# opendeep_pba001_eval_v01.net
KiCad netlist of a schematic drawn in EasyEDA Pro
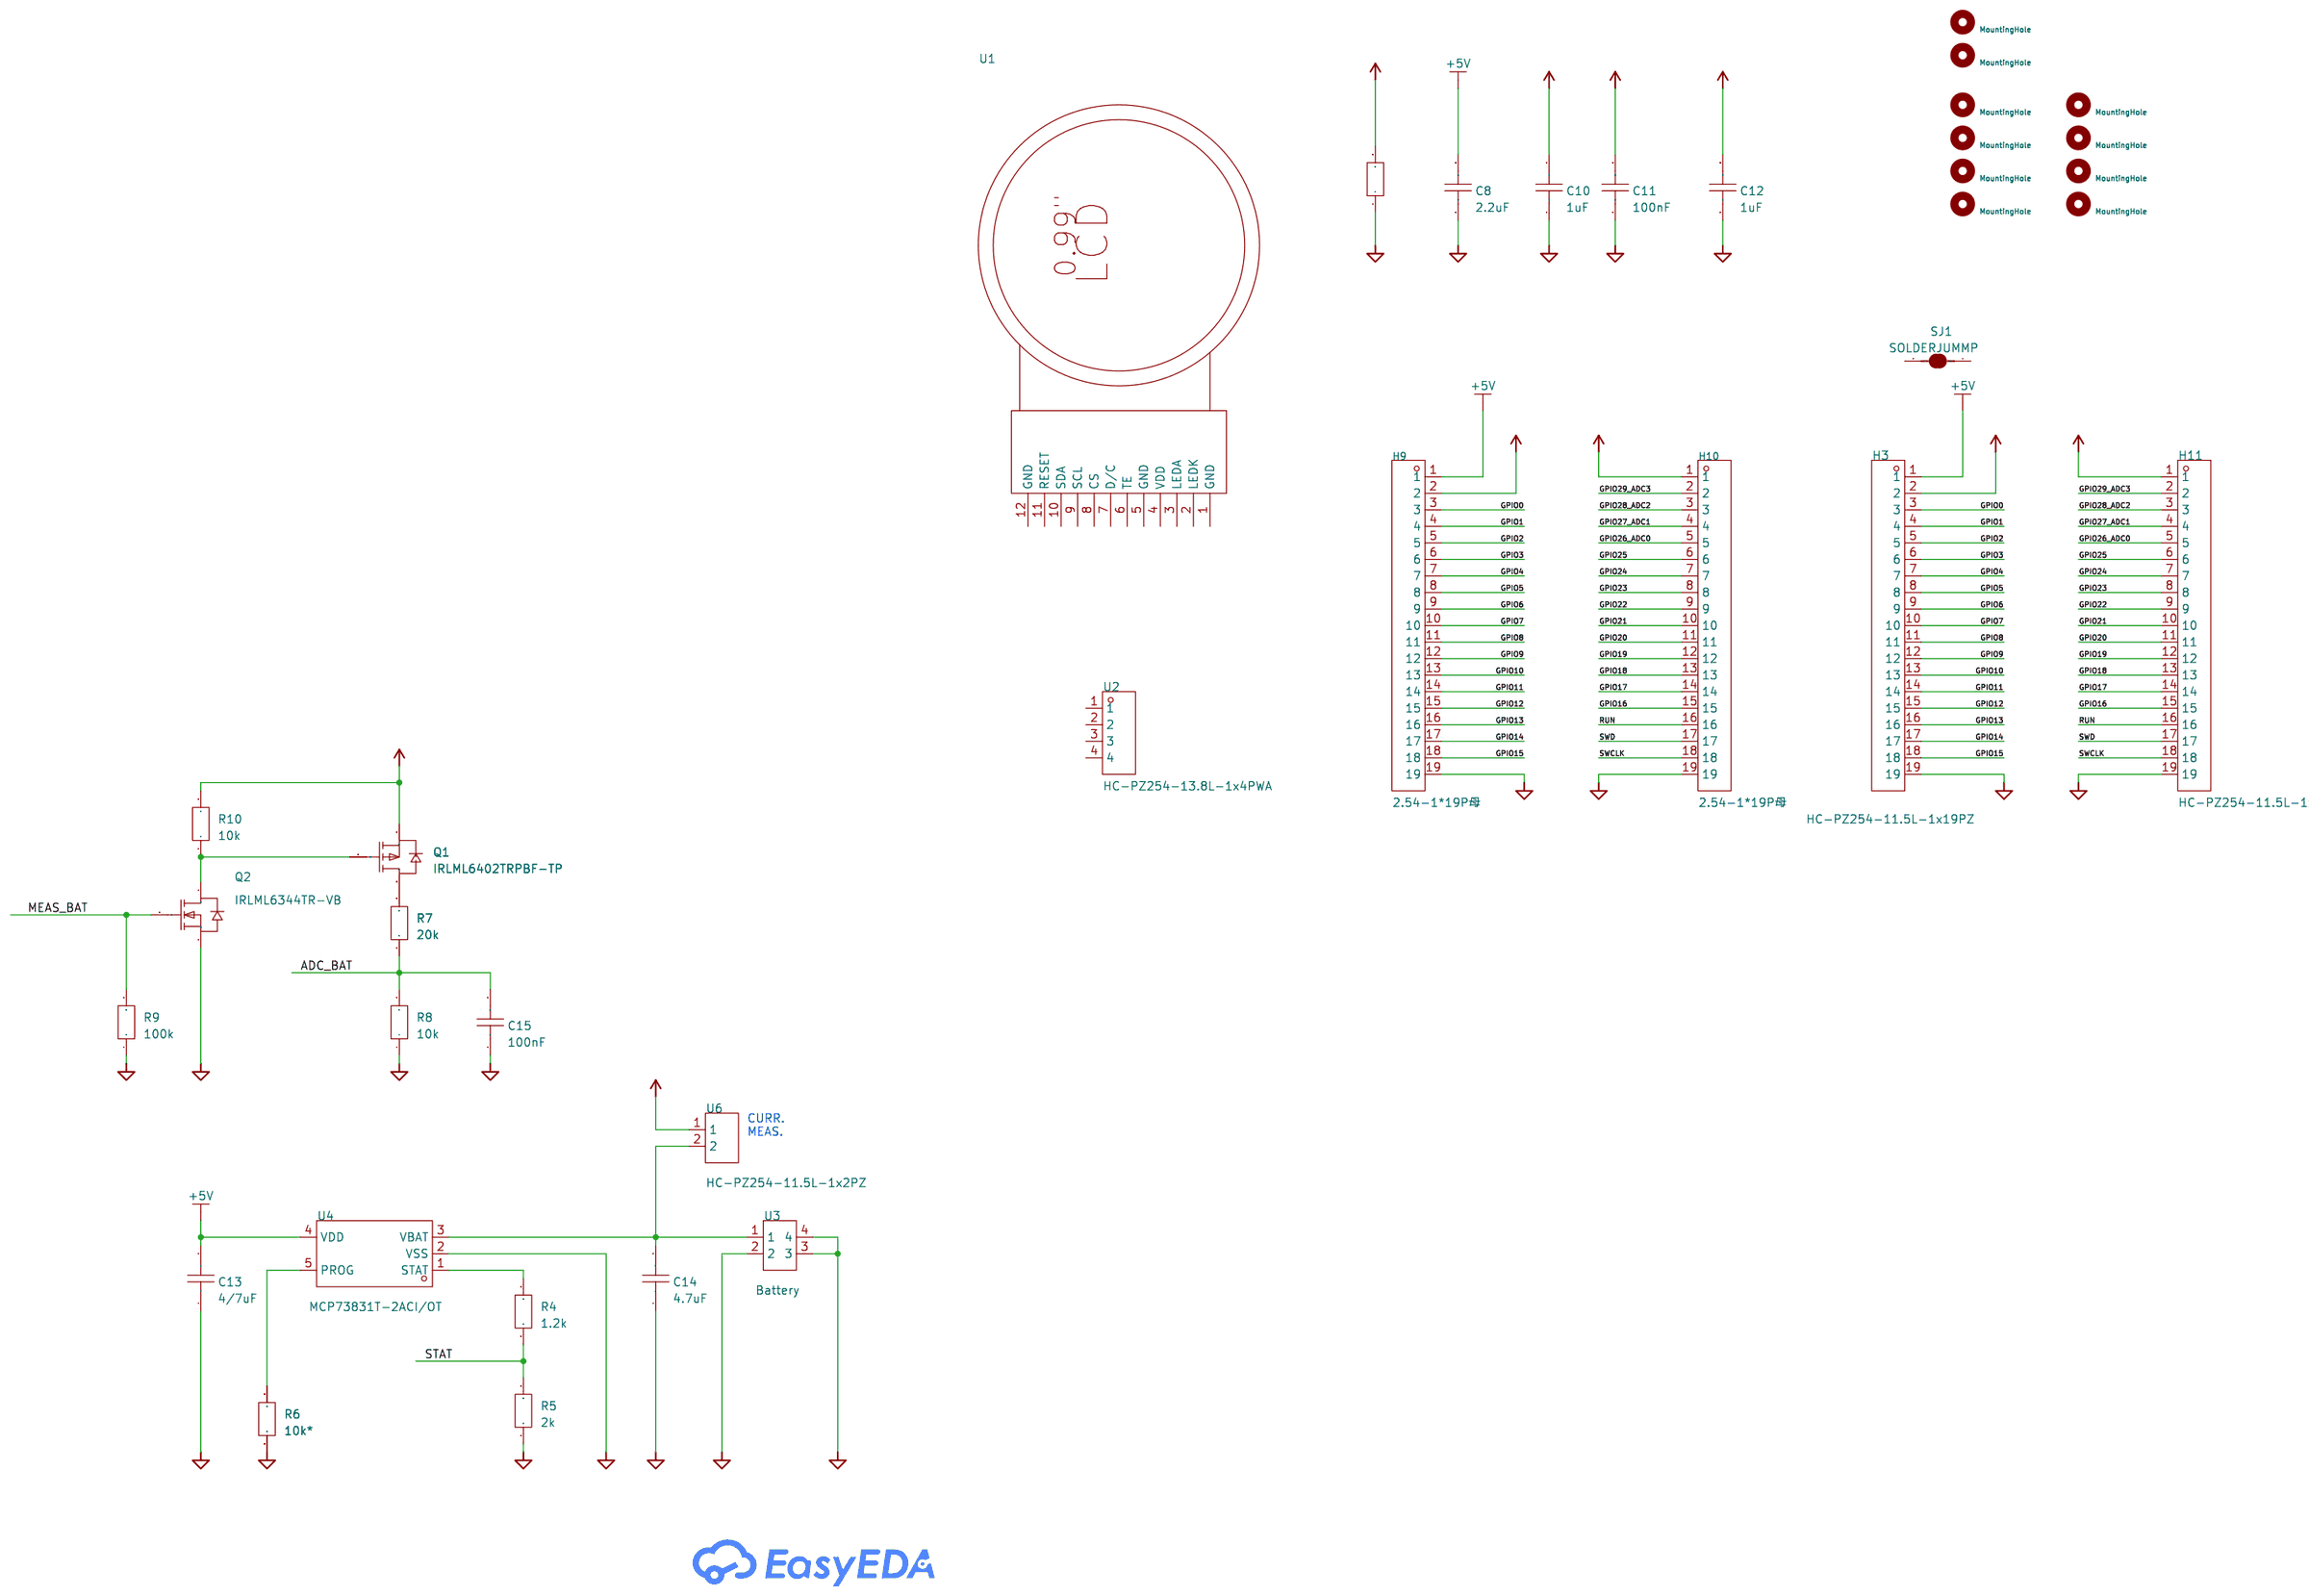
[diagram p0: schematic sheet]

(export (version "E")
  (design (tool "Eeschema 10.0.6"))
  (components
    (comp (ref "C8")
      (value "2.2uF")
      (footprint "easyedapro:C0603")
      (description "Capacitance:1nF Tolerance:±5% Tolerance:±5% Voltage Rating:200V Temperature Coefficient:C0G")
      (fields
        (field (name "Manufacturer Part") "C0603C102J2GECAUTO")
        (field (name "Manufacturer") "KEMET(基美)")
      )
      (libsource (lib "easyedapro") (part "C0603C102J2GECAUTO"))
    )
    (comp (ref "C10")
      (value "1uF")
      (footprint "easyedapro:C0603")
      (description "Capacitance:1nF Tolerance:±5% Tolerance:±5% Voltage Rating:200V Temperature Coefficient:C0G")
      (fields
        (field (name "Manufacturer Part") "C0603C102J2GECAUTO")
        (field (name "Manufacturer") "KEMET(基美)")
      )
      (libsource (lib "easyedapro") (part "C0603C102J2GECAUTO"))
    )
    (comp (ref "C11")
      (value "100nF")
      (footprint "easyedapro:C0603")
      (description "Capacitance:1nF Tolerance:±5% Tolerance:±5% Voltage Rating:200V Temperature Coefficient:C0G")
      (fields
        (field (name "Manufacturer Part") "C0603C102J2GECAUTO")
        (field (name "Manufacturer") "KEMET(基美)")
      )
      (libsource (lib "easyedapro") (part "C0603C102J2GECAUTO"))
    )
    (comp (ref "C12")
      (value "1uF")
      (footprint "easyedapro:C0603")
      (description "Capacitance:1nF Tolerance:±5% Tolerance:±5% Voltage Rating:200V Temperature Coefficient:C0G")
      (fields
        (field (name "Manufacturer Part") "C0603C102J2GECAUTO")
        (field (name "Manufacturer") "KEMET(基美)")
      )
      (libsource (lib "easyedapro") (part "C0603C102J2GECAUTO"))
    )
    (comp (ref "C13")
      (value "4/7uF")
      (footprint "easyedapro:C0603")
      (description "Capacitance:1nF Tolerance:±5% Tolerance:±5% Voltage Rating:200V Temperature Coefficient:C0G")
      (fields
        (field (name "Manufacturer Part") "C0603C102J2GECAUTO")
        (field (name "Manufacturer") "KEMET(基美)")
      )
      (libsource (lib "easyedapro") (part "C0603C102J2GECAUTO"))
    )
    (comp (ref "C14")
      (value "4.7uF")
      (footprint "easyedapro:C0603")
      (description "Capacitance:1nF Tolerance:±5% Tolerance:±5% Voltage Rating:200V Temperature Coefficient:C0G")
      (fields
        (field (name "Manufacturer Part") "C0603C102J2GECAUTO")
        (field (name "Manufacturer") "KEMET(基美)")
      )
      (libsource (lib "easyedapro") (part "C0603C102J2GECAUTO"))
    )
    (comp (ref "C15")
      (value "100nF")
      (footprint "easyedapro:C0603")
      (description "Capacitance:1nF Tolerance:±5% Tolerance:±5% Voltage Rating:200V Temperature Coefficient:C0G")
      (fields
        (field (name "Manufacturer Part") "C0603C102J2GECAUTO")
        (field (name "Manufacturer") "KEMET(基美)")
      )
      (libsource (lib "easyedapro") (part "C0603C102J2GECAUTO"))
    )
    (comp (ref "H1")
      (value "MountingHole")
      (footprint "easyedapro:MountingHole:MountingHole_2.7mm_M2.5")
      (libsource (lib "easyedapro") (part "Mechanical_MountingHole"))
    )
    (comp (ref "H2")
      (value "MountingHole")
      (footprint "easyedapro:MountingHole:MountingHole_2.7mm_M2.5")
      (libsource (lib "easyedapro") (part "Mechanical_MountingHole"))
    )
    (comp (ref "H3")
      (value "HC-PZ254-11.5L-1x19PZ")
      (footprint "easyedapro:HDR-TH_19P-P2.54-V-M")
      (fields (field (name "Manufacturer") "HC(虹成电子)"))
      (libsource (lib "easyedapro") (part "HC-PZ254-11.5L-1X19PZ"))
    )
    (comp (ref "H5")
      (value "MountingHole")
      (footprint "easyedapro:MountingHole:MountingHole_2.7mm_M2.5")
      (libsource (lib "easyedapro") (part "Mechanical_MountingHole"))
    )
    (comp (ref "H6")
      (value "MountingHole")
      (footprint "easyedapro:MountingHole:MountingHole_2.7mm_M2.5")
      (libsource (lib "easyedapro") (part "Mechanical_MountingHole"))
    )
    (comp (ref "H7")
      (value "MountingHole")
      (footprint "easyedapro:MountingHole:MountingHole_2.7mm_M2.5")
      (libsource (lib "easyedapro") (part "Mechanical_MountingHole"))
    )
    (comp (ref "H8")
      (value "MountingHole")
      (footprint "easyedapro:MountingHole:MountingHole_2.7mm_M2.5")
      (libsource (lib "easyedapro") (part "Mechanical_MountingHole"))
    )
    (comp (ref "H9")
      (value "2.54-1*19P母")
      (footprint "easyedapro:HDR-TH_19P-P2.54-V-F")
      (fields (field (name "Manufacturer") "BOOMELE(博穆精密)"))
      (libsource (lib "easyedapro") (part "2.54-1*19P母"))
    )
    (comp (ref "H10")
      (value "2.54-1*19P母")
      (footprint "easyedapro:HDR-TH_19P-P2.54-V-F")
      (fields (field (name "Manufacturer") "BOOMELE(博穆精密)"))
      (libsource (lib "easyedapro") (part "2.54-1*19P母"))
    )
    (comp (ref "H11")
      (value "HC-PZ254-11.5L-1x19PZ")
      (footprint "easyedapro:HDR-TH_19P-P2.54-V-M")
      (fields (field (name "Manufacturer") "HC(虹成电子)"))
      (libsource (lib "easyedapro") (part "HC-PZ254-11.5L-1X19PZ"))
    )
    (comp (ref "H12")
      (value "MountingHole")
      (footprint "easyedapro:MountingHole:MountingHole_2.7mm_M2.5")
      (libsource (lib "easyedapro") (part "Mechanical_MountingHole"))
    )
    (comp (ref "H13")
      (value "MountingHole")
      (footprint "easyedapro:MountingHole:MountingHole_2.7mm_M2.5")
      (libsource (lib "easyedapro") (part "Mechanical_MountingHole"))
    )
    (comp (ref "H14")
      (value "MountingHole")
      (footprint "easyedapro:MountingHole:MountingHole_2.7mm_M2.5")
      (libsource (lib "easyedapro") (part "Mechanical_MountingHole"))
    )
    (comp (ref "H15")
      (value "MountingHole")
      (footprint "easyedapro:MountingHole:MountingHole_2.7mm_M2.5")
      (libsource (lib "easyedapro") (part "Mechanical_MountingHole"))
    )
    (comp (ref "Q1")
      (value "IRLML6402TRPBF-TP")
      (footprint "easyedapro:SOT-23-3_L2.9-W1.3-P1.90-LS2.4-BR")
      (fields (field (name "Manufacturer") "TECH PUBLIC(台舟)"))
      (libsource (lib "easyedapro") (part "IRLML6402TRPBF-TP"))
    )
    (comp (ref "Q2")
      (value "IRLML6344TR-VB")
      (footprint "easyedapro:SOT-23-3_L2.9-W1.3-P1.90-LS2.4-BR")
      (fields (field (name "Manufacturer") "VBsemi(微碧半导体)"))
      (libsource (lib "easyedapro") (part "IRLML6344TR"))
    )
    (comp (ref "R3")
      (value "DNF")
      (footprint "easyedapro:R0603")
      (fields (field (name "Manufacturer Part") "RCC06031K50FKEA") (field (name "Manufacturer") "VISHAY(威世)"))
      (libsource (lib "easyedapro") (part "RCC06031K50FKEA"))
    )
    (comp (ref "R4")
      (value "1.2k")
      (footprint "easyedapro:R0603")
      (fields (field (name "Manufacturer Part") "RCC06031K50FKEA") (field (name "Manufacturer") "VISHAY(威世)"))
      (libsource (lib "easyedapro") (part "RCC06031K50FKEA"))
    )
    (comp (ref "R5")
      (value "2k")
      (footprint "easyedapro:R0603")
      (fields (field (name "Manufacturer Part") "RCC06031K50FKEA") (field (name "Manufacturer") "VISHAY(威世)"))
      (libsource (lib "easyedapro") (part "RCC06031K50FKEA"))
    )
    (comp (ref "R6")
      (value "10k*")
      (footprint "easyedapro:R0603")
      (fields (field (name "Manufacturer Part") "RCC06031K50FKEA") (field (name "Manufacturer") "VISHAY(威世)"))
      (libsource (lib "easyedapro") (part "RCC06031K50FKEA"))
    )
    (comp (ref "R7")
      (value "20k")
      (footprint "easyedapro:R0603")
      (fields (field (name "Manufacturer Part") "RCC06031K50FKEA") (field (name "Manufacturer") "VISHAY(威世)"))
      (libsource (lib "easyedapro") (part "RCC06031K50FKEA"))
    )
    (comp (ref "R8")
      (value "10k")
      (footprint "easyedapro:R0603")
      (fields (field (name "Manufacturer Part") "RCC06031K50FKEA") (field (name "Manufacturer") "VISHAY(威世)"))
      (libsource (lib "easyedapro") (part "RCC06031K50FKEA"))
    )
    (comp (ref "R9")
      (value "100k")
      (footprint "easyedapro:R0603")
      (fields (field (name "Manufacturer Part") "RCC06031K50FKEA") (field (name "Manufacturer") "VISHAY(威世)"))
      (libsource (lib "easyedapro") (part "RCC06031K50FKEA"))
    )
    (comp (ref "R10")
      (value "10k")
      (footprint "easyedapro:R0603")
      (fields (field (name "Manufacturer Part") "RCC06031K50FKEA") (field (name "Manufacturer") "VISHAY(威世)"))
      (libsource (lib "easyedapro") (part "RCC06031K50FKEA"))
    )
    (comp (ref "SJ1")
      (value "SOLDERJUMMP")
      (footprint "easyedapro:SJ_2S-NO")
      (fields (field (name "Contributor") "SparkFun"))
      (libsource (lib "easyedapro") (part "SOLDERJUMPERNO"))
    )
    (comp (ref "U1")
      (value "~")
      (footprint "easyedapro:LCD 0.99")
      (libsource (lib "easyedapro") (part "LCD 0.99"))
    )
    (comp (ref "U2")
      (value "HC-PZ254-13.8L-1x4PWA")
      (footprint "easyedapro:HDR-TH_4P-P2.54-H-M_HC-PZ254-13.8L-1X4PWA")
      (fields (field (name "Manufacturer") "HC(虹成电子)"))
      (libsource (lib "easyedapro") (part "HC-PZ254-13.8L-1X4PWA"))
    )
    (comp (ref "U3")
      (value "Battery")
      (footprint "easyedapro:CONN-SMD_2.0-2PWT")
      (libsource (lib "easyedapro") (part "BATTERY"))
    )
    (comp (ref "U4")
      (value "MCP73831T-2ACI/OT")
      (footprint "easyedapro:SOT-23-5_L3.0-W1.7-P0.95-LS2.8-BL")
      (fields (field (name "Manufacturer") "MICROCHIP(美国微芯)"))
      (libsource (lib "easyedapro") (part "MCP73831T-2ACI/OT"))
    )
    (comp (ref "U6")
      (value "HC-PZ254-11.5L-1x2PZ")
      (footprint "easyedapro:CONN-TH_HC-PZ254-11.5L-1X2PZ")
      (fields (field (name "Manufacturer") "HC(虹成电子)"))
      (libsource (lib "easyedapro") (part "HC-PZ254-11.5L-1X2PZ"))
    )
  )
  (nets
    (net (code "1") (name "+5V") (class "Default")
      (node (ref "C13") (pin "2") (pinfunction "2_2") (pintype "unspecified"))
      (node (ref "C8") (pin "2") (pinfunction "2_2") (pintype "unspecified"))
      (node (ref "H3") (pin "1") (pinfunction "1_1") (pintype "unspecified"))
      (node (ref "H9") (pin "1") (pinfunction "1_1") (pintype "input"))
      (node (ref "U4") (pin "4") (pinfunction "VDD_4") (pintype "unspecified"))
    )
    (net (code "2") (name "/ADC_BAT") (class "Default")
      (node (ref "C15") (pin "2") (pinfunction "2_2") (pintype "unspecified"))
      (node (ref "R7") (pin "1") (pinfunction "1_1") (pintype "unspecified"))
      (node (ref "R8") (pin "2") (pinfunction "2_2") (pintype "unspecified"))
    )
    (net (code "3") (name "/GPIO0") (class "Default")
      (node (ref "H3") (pin "3") (pinfunction "3_3") (pintype "unspecified"))
      (node (ref "H9") (pin "3") (pinfunction "3_3") (pintype "input"))
    )
    (net (code "4") (name "/GPIO1") (class "Default")
      (node (ref "H3") (pin "4") (pinfunction "4_4") (pintype "unspecified"))
      (node (ref "H9") (pin "4") (pinfunction "4_4") (pintype "input"))
    )
    (net (code "5") (name "/GPIO2") (class "Default")
      (node (ref "H3") (pin "5") (pinfunction "5_5") (pintype "unspecified"))
      (node (ref "H9") (pin "5") (pinfunction "5_5") (pintype "input"))
    )
    (net (code "6") (name "/GPIO3") (class "Default")
      (node (ref "H3") (pin "6") (pinfunction "6_6") (pintype "unspecified"))
      (node (ref "H9") (pin "6") (pinfunction "6_6") (pintype "input"))
    )
    (net (code "7") (name "/GPIO4") (class "Default")
      (node (ref "H3") (pin "7") (pinfunction "7_7") (pintype "unspecified"))
      (node (ref "H9") (pin "7") (pinfunction "7_7") (pintype "input"))
    )
    (net (code "8") (name "/GPIO5") (class "Default")
      (node (ref "H3") (pin "8") (pinfunction "8_8") (pintype "unspecified"))
      (node (ref "H9") (pin "8") (pinfunction "8_8") (pintype "input"))
    )
    (net (code "9") (name "/GPIO6") (class "Default")
      (node (ref "H3") (pin "9") (pinfunction "9_9") (pintype "unspecified"))
      (node (ref "H9") (pin "9") (pinfunction "9_9") (pintype "input"))
    )
    (net (code "10") (name "/GPIO7") (class "Default")
      (node (ref "H3") (pin "10") (pinfunction "10_10") (pintype "unspecified"))
      (node (ref "H9") (pin "10") (pinfunction "10_10") (pintype "input"))
    )
    (net (code "11") (name "/GPIO8") (class "Default")
      (node (ref "H3") (pin "11") (pinfunction "11_11") (pintype "unspecified"))
      (node (ref "H9") (pin "11") (pinfunction "11_11") (pintype "input"))
    )
    (net (code "12") (name "/GPIO9") (class "Default")
      (node (ref "H3") (pin "12") (pinfunction "12_12") (pintype "unspecified"))
      (node (ref "H9") (pin "12") (pinfunction "12_12") (pintype "input"))
    )
    (net (code "13") (name "/GPIO10") (class "Default")
      (node (ref "H3") (pin "13") (pinfunction "13_13") (pintype "unspecified"))
      (node (ref "H9") (pin "13") (pinfunction "13_13") (pintype "input"))
    )
    (net (code "14") (name "/GPIO11") (class "Default")
      (node (ref "H3") (pin "14") (pinfunction "14_14") (pintype "unspecified"))
      (node (ref "H9") (pin "14") (pinfunction "14_14") (pintype "input"))
    )
    (net (code "15") (name "/GPIO12") (class "Default")
      (node (ref "H3") (pin "15") (pinfunction "15_15") (pintype "unspecified"))
      (node (ref "H9") (pin "15") (pinfunction "15_15") (pintype "input"))
    )
    (net (code "16") (name "/GPIO13") (class "Default")
      (node (ref "H3") (pin "16") (pinfunction "16_16") (pintype "unspecified"))
      (node (ref "H9") (pin "16") (pinfunction "16_16") (pintype "input"))
    )
    (net (code "17") (name "/GPIO14") (class "Default")
      (node (ref "H3") (pin "17") (pinfunction "17_17") (pintype "unspecified"))
      (node (ref "H9") (pin "17") (pinfunction "17_17") (pintype "input"))
    )
    (net (code "18") (name "/GPIO15") (class "Default")
      (node (ref "H3") (pin "18") (pinfunction "18_18") (pintype "unspecified"))
      (node (ref "H9") (pin "18") (pinfunction "18_18") (pintype "input"))
    )
    (net (code "19") (name "/GPIO16") (class "Default")
      (node (ref "H10") (pin "15") (pinfunction "15_15") (pintype "input"))
      (node (ref "H11") (pin "15") (pinfunction "15_15") (pintype "unspecified"))
    )
    (net (code "20") (name "/GPIO17") (class "Default")
      (node (ref "H10") (pin "14") (pinfunction "14_14") (pintype "input"))
      (node (ref "H11") (pin "14") (pinfunction "14_14") (pintype "unspecified"))
    )
    (net (code "21") (name "/GPIO18") (class "Default")
      (node (ref "H10") (pin "13") (pinfunction "13_13") (pintype "input"))
      (node (ref "H11") (pin "13") (pinfunction "13_13") (pintype "unspecified"))
    )
    (net (code "22") (name "/GPIO19") (class "Default")
      (node (ref "H10") (pin "12") (pinfunction "12_12") (pintype "input"))
      (node (ref "H11") (pin "12") (pinfunction "12_12") (pintype "unspecified"))
    )
    (net (code "23") (name "/GPIO20") (class "Default")
      (node (ref "H10") (pin "11") (pinfunction "11_11") (pintype "input"))
      (node (ref "H11") (pin "11") (pinfunction "11_11") (pintype "unspecified"))
    )
    (net (code "24") (name "/GPIO21") (class "Default")
      (node (ref "H10") (pin "10") (pinfunction "10_10") (pintype "input"))
      (node (ref "H11") (pin "10") (pinfunction "10_10") (pintype "unspecified"))
    )
    (net (code "25") (name "/GPIO22") (class "Default")
      (node (ref "H10") (pin "9") (pinfunction "9_9") (pintype "input"))
      (node (ref "H11") (pin "9") (pinfunction "9_9") (pintype "unspecified"))
    )
    (net (code "26") (name "/GPIO23") (class "Default")
      (node (ref "H10") (pin "8") (pinfunction "8_8") (pintype "input"))
      (node (ref "H11") (pin "8") (pinfunction "8_8") (pintype "unspecified"))
    )
    (net (code "27") (name "/GPIO24") (class "Default")
      (node (ref "H10") (pin "7") (pinfunction "7_7") (pintype "input"))
      (node (ref "H11") (pin "7") (pinfunction "7_7") (pintype "unspecified"))
    )
    (net (code "28") (name "/GPIO25") (class "Default")
      (node (ref "H10") (pin "6") (pinfunction "6_6") (pintype "input"))
      (node (ref "H11") (pin "6") (pinfunction "6_6") (pintype "unspecified"))
    )
    (net (code "29") (name "/GPIO26_ADC0") (class "Default")
      (node (ref "H10") (pin "5") (pinfunction "5_5") (pintype "input"))
      (node (ref "H11") (pin "5") (pinfunction "5_5") (pintype "unspecified"))
    )
    (net (code "30") (name "/GPIO27_ADC1") (class "Default")
      (node (ref "H10") (pin "4") (pinfunction "4_4") (pintype "input"))
      (node (ref "H11") (pin "4") (pinfunction "4_4") (pintype "unspecified"))
    )
    (net (code "31") (name "/GPIO28_ADC2") (class "Default")
      (node (ref "H10") (pin "3") (pinfunction "3_3") (pintype "input"))
      (node (ref "H11") (pin "3") (pinfunction "3_3") (pintype "unspecified"))
    )
    (net (code "32") (name "/GPIO29_ADC3") (class "Default")
      (node (ref "H10") (pin "2") (pinfunction "2_2") (pintype "input"))
      (node (ref "H11") (pin "2") (pinfunction "2_2") (pintype "unspecified"))
    )
    (net (code "33") (name "/MEAS_BAT") (class "Default")
      (node (ref "Q2") (pin "1") (pinfunction "G_1") (pintype "unspecified"))
      (node (ref "R9") (pin "2") (pinfunction "2_2") (pintype "unspecified"))
    )
    (net (code "34") (name "/RUN") (class "Default")
      (node (ref "H10") (pin "16") (pinfunction "16_16") (pintype "input"))
      (node (ref "H11") (pin "16") (pinfunction "16_16") (pintype "unspecified"))
    )
    (net (code "35") (name "/STAT") (class "Default")
      (node (ref "R4") (pin "1") (pinfunction "1_1") (pintype "unspecified"))
      (node (ref "R5") (pin "2") (pinfunction "2_2") (pintype "unspecified"))
    )
    (net (code "36") (name "/SWCLK") (class "Default")
      (node (ref "H10") (pin "18") (pinfunction "18_18") (pintype "input"))
      (node (ref "H11") (pin "18") (pinfunction "18_18") (pintype "unspecified"))
    )
    (net (code "37") (name "/SWD") (class "Default")
      (node (ref "H10") (pin "17") (pinfunction "17_17") (pintype "input"))
      (node (ref "H11") (pin "17") (pinfunction "17_17") (pintype "unspecified"))
    )
    (net (code "38") (name "Net-(Q1-D)") (class "Default")
      (node (ref "Q1") (pin "3") (pinfunction "D_3") (pintype "unspecified"))
      (node (ref "R7") (pin "2") (pinfunction "2_2") (pintype "unspecified"))
    )
    (net (code "39") (name "Net-(Q1-G)") (class "Default")
      (node (ref "Q1") (pin "1") (pinfunction "G_1") (pintype "unspecified"))
      (node (ref "Q2") (pin "3") (pinfunction "D_3") (pintype "unspecified"))
      (node (ref "R10") (pin "1") (pinfunction "1_1") (pintype "unspecified"))
    )
    (net (code "40") (name "Net-(U4-PROG)") (class "Default")
      (node (ref "R6") (pin "2") (pinfunction "2_2") (pintype "unspecified"))
      (node (ref "U4") (pin "5") (pinfunction "PROG_5") (pintype "unspecified"))
    )
    (net (code "41") (name "Net-(U4-STAT)") (class "Default")
      (node (ref "R4") (pin "2") (pinfunction "2_2") (pintype "unspecified"))
      (node (ref "U4") (pin "1") (pinfunction "STAT_1") (pintype "unspecified"))
    )
    (net (code "42") (name "Net-(U4-VBAT)") (class "Default")
      (node (ref "C14") (pin "2") (pinfunction "2_2") (pintype "unspecified"))
      (node (ref "U3") (pin "1") (pinfunction "1_1") (pintype "unspecified"))
      (node (ref "U4") (pin "3") (pinfunction "VBAT_3") (pintype "unspecified"))
      (node (ref "U6") (pin "2") (pinfunction "2_2") (pintype "unspecified"))
    )
    (net (code "43") (name "POWER_+3V3") (class "Default")
      (node (ref "C10") (pin "2") (pinfunction "2_2") (pintype "unspecified"))
      (node (ref "C11") (pin "2") (pinfunction "2_2") (pintype "unspecified"))
      (node (ref "C12") (pin "2") (pinfunction "2_2") (pintype "unspecified"))
      (node (ref "H10") (pin "1") (pinfunction "1_1") (pintype "input"))
      (node (ref "H11") (pin "1") (pinfunction "1_1") (pintype "unspecified"))
      (node (ref "H3") (pin "2") (pinfunction "2_2") (pintype "unspecified"))
      (node (ref "H9") (pin "2") (pinfunction "2_2") (pintype "input"))
      (node (ref "R3") (pin "2") (pinfunction "2_2") (pintype "unspecified"))
    )
    (net (code "44") (name "POWER_BAT") (class "Default")
      (node (ref "Q1") (pin "2") (pinfunction "S_2") (pintype "unspecified"))
      (node (ref "R10") (pin "2") (pinfunction "2_2") (pintype "unspecified"))
      (node (ref "U6") (pin "1") (pinfunction "1_1") (pintype "unspecified"))
    )
    (net (code "45") (name "POWER_GND") (class "Default")
      (node (ref "C10") (pin "1") (pinfunction "1_1") (pintype "unspecified"))
      (node (ref "C11") (pin "1") (pinfunction "1_1") (pintype "unspecified"))
      (node (ref "C12") (pin "1") (pinfunction "1_1") (pintype "unspecified"))
      (node (ref "C13") (pin "1") (pinfunction "1_1") (pintype "unspecified"))
      (node (ref "C14") (pin "1") (pinfunction "1_1") (pintype "unspecified"))
      (node (ref "C15") (pin "1") (pinfunction "1_1") (pintype "unspecified"))
      (node (ref "C8") (pin "1") (pinfunction "1_1") (pintype "unspecified"))
      (node (ref "H10") (pin "19") (pinfunction "19_19") (pintype "input"))
      (node (ref "H11") (pin "19") (pinfunction "19_19") (pintype "unspecified"))
      (node (ref "H3") (pin "19") (pinfunction "19_19") (pintype "unspecified"))
      (node (ref "H9") (pin "19") (pinfunction "19_19") (pintype "input"))
      (node (ref "Q2") (pin "2") (pinfunction "S_2") (pintype "unspecified"))
      (node (ref "R3") (pin "1") (pinfunction "1_1") (pintype "unspecified"))
      (node (ref "R5") (pin "1") (pinfunction "1_1") (pintype "unspecified"))
      (node (ref "R6") (pin "1") (pinfunction "1_1") (pintype "unspecified"))
      (node (ref "R8") (pin "1") (pinfunction "1_1") (pintype "unspecified"))
      (node (ref "R9") (pin "1") (pinfunction "1_1") (pintype "unspecified"))
      (node (ref "U3") (pin "2") (pinfunction "2_2") (pintype "unspecified"))
      (node (ref "U3") (pin "3") (pinfunction "3_3") (pintype "unspecified"))
      (node (ref "U3") (pin "4") (pinfunction "4_4") (pintype "unspecified"))
      (node (ref "U4") (pin "2") (pinfunction "VSS_2") (pintype "unspecified"))
    )
    (net (code "46") (name "unconnected-(SJ1-Pad1)") (class "Default")
      (node (ref "SJ1") (pin "1") (pinfunction "1_1") (pintype "unspecified"))
    )
    (net (code "47") (name "unconnected-(SJ1-Pad2)") (class "Default")
      (node (ref "SJ1") (pin "2") (pinfunction "2_2") (pintype "unspecified"))
    )
    (net (code "48") (name "unconnected-(U1-CS-Pad8)") (class "Default")
      (node (ref "U1") (pin "8") (pinfunction "CS_8") (pintype "input"))
    )
    (net (code "49") (name "unconnected-(U1-D{slash}C-Pad7)") (class "Default")
      (node (ref "U1") (pin "7") (pinfunction "D/C_7") (pintype "input"))
    )
    (net (code "50") (name "unconnected-(U1-GND-Pad1)") (class "Default")
      (node (ref "U1") (pin "1") (pinfunction "GND_1") (pintype "input"))
    )
    (net (code "51") (name "unconnected-(U1-GND-Pad5)") (class "Default")
      (node (ref "U1") (pin "5") (pinfunction "GND_5") (pintype "input"))
    )
    (net (code "52") (name "unconnected-(U1-GND-Pad12)") (class "Default")
      (node (ref "U1") (pin "12") (pinfunction "GND_12") (pintype "input"))
    )
    (net (code "53") (name "unconnected-(U1-LEDA-Pad3)") (class "Default")
      (node (ref "U1") (pin "3") (pinfunction "LEDA_3") (pintype "input"))
    )
    (net (code "54") (name "unconnected-(U1-LEDK-Pad2)") (class "Default")
      (node (ref "U1") (pin "2") (pinfunction "LEDK_2") (pintype "input"))
    )
    (net (code "55") (name "unconnected-(U1-RESET-Pad11)") (class "Default")
      (node (ref "U1") (pin "11") (pinfunction "RESET_11") (pintype "input"))
    )
    (net (code "56") (name "unconnected-(U1-SCL-Pad9)") (class "Default")
      (node (ref "U1") (pin "9") (pinfunction "SCL_9") (pintype "input"))
    )
    (net (code "57") (name "unconnected-(U1-SDA-Pad10)") (class "Default")
      (node (ref "U1") (pin "10") (pinfunction "SDA_10") (pintype "input"))
    )
    (net (code "58") (name "unconnected-(U1-TE-Pad6)") (class "Default")
      (node (ref "U1") (pin "6") (pinfunction "TE_6") (pintype "input"))
    )
    (net (code "59") (name "unconnected-(U1-VDD-Pad4)") (class "Default")
      (node (ref "U1") (pin "4") (pinfunction "VDD_4") (pintype "input"))
    )
    (net (code "60") (name "unconnected-(U2-Pad1)") (class "Default")
      (node (ref "U2") (pin "1") (pinfunction "1_1") (pintype "unspecified"))
    )
    (net (code "61") (name "unconnected-(U2-Pad2)") (class "Default")
      (node (ref "U2") (pin "2") (pinfunction "2_2") (pintype "unspecified"))
    )
    (net (code "62") (name "unconnected-(U2-Pad3)") (class "Default")
      (node (ref "U2") (pin "3") (pinfunction "3_3") (pintype "unspecified"))
    )
    (net (code "63") (name "unconnected-(U2-Pad4)") (class "Default")
      (node (ref "U2") (pin "4") (pinfunction "4_4") (pintype "unspecified"))
    )
  )
)
